# con-left-bot.net
KiCad netlist of a schematic drawn in Altium Designer
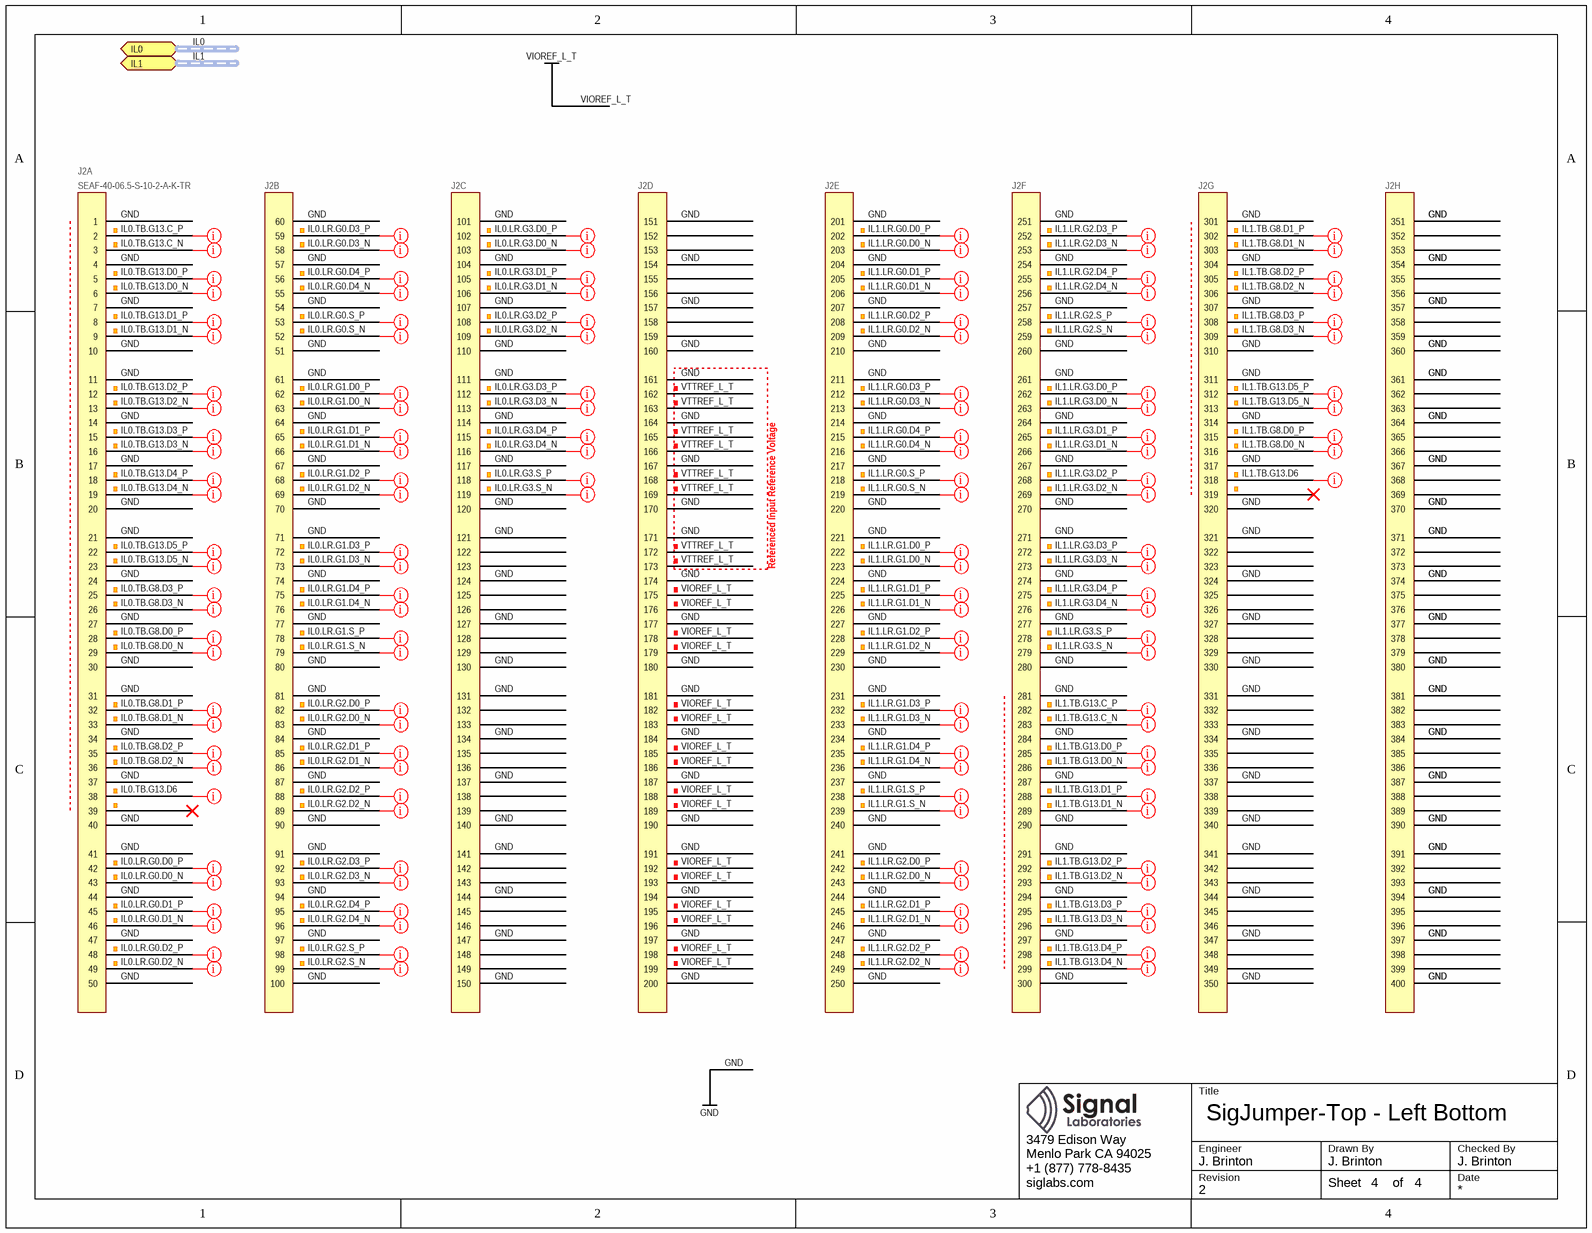
[diagram p0: con-left-bot.SchDoc]

(export (version "E")
  (design (tool "Eeschema 10.0.6"))
  (components
    (comp (ref "J2")
      (value "SEAF-40-06.5-S-10-2-A-K-TR")
      (footprint "samtec:SEAF-40-06.5-S-10-2-A-K-TR")
      (description "Terminal Array Assembly, Surface Mount, 0.050\" Pitch, 400 Pins")
      (fields (field (name "MANUFACTURER") "Samtec"))
      (libsource (lib "samtec") (part "SEAF-40-06.5-S-10-2-A-K-TR"))
    )
  )
  (nets
    (net (code "3") (name "/IL0.LR.G0.D0_N") (class "Default")
      (node (ref "J2") (pin "43") (pinfunction "43_43") (pintype "passive"))
    )
    (net (code "4") (name "/IL0.LR.G0.D0_P") (class "Default")
      (node (ref "J2") (pin "42") (pinfunction "42_42") (pintype "passive"))
    )
    (net (code "5") (name "/IL0.LR.G0.D1_N") (class "Default")
      (node (ref "J2") (pin "46") (pinfunction "46_46") (pintype "passive"))
    )
    (net (code "6") (name "/IL0.LR.G0.D1_P") (class "Default")
      (node (ref "J2") (pin "45") (pinfunction "45_45") (pintype "passive"))
    )
    (net (code "7") (name "/IL0.LR.G0.D2_N") (class "Default")
      (node (ref "J2") (pin "49") (pinfunction "49_49") (pintype "passive"))
    )
    (net (code "8") (name "/IL0.LR.G0.D2_P") (class "Default")
      (node (ref "J2") (pin "48") (pinfunction "48_48") (pintype "passive"))
    )
    (net (code "9") (name "/IL0.LR.G0.D3_N") (class "Default")
      (node (ref "J2") (pin "58") (pinfunction "58_58") (pintype "passive"))
    )
    (net (code "10") (name "/IL0.LR.G0.D3_P") (class "Default")
      (node (ref "J2") (pin "59") (pinfunction "59_59") (pintype "passive"))
    )
    (net (code "11") (name "/IL0.LR.G0.D4_N") (class "Default")
      (node (ref "J2") (pin "55") (pinfunction "55_55") (pintype "passive"))
    )
    (net (code "12") (name "/IL0.LR.G0.D4_P") (class "Default")
      (node (ref "J2") (pin "56") (pinfunction "56_56") (pintype "passive"))
    )
    (net (code "13") (name "/IL0.LR.G0.S_N") (class "Default")
      (node (ref "J2") (pin "52") (pinfunction "52_52") (pintype "passive"))
    )
    (net (code "14") (name "/IL0.LR.G0.S_P") (class "Default")
      (node (ref "J2") (pin "53") (pinfunction "53_53") (pintype "passive"))
    )
    (net (code "15") (name "/IL0.LR.G1.D0_N") (class "Default")
      (node (ref "J2") (pin "63") (pinfunction "63_63") (pintype "passive"))
    )
    (net (code "16") (name "/IL0.LR.G1.D0_P") (class "Default")
      (node (ref "J2") (pin "62") (pinfunction "62_62") (pintype "passive"))
    )
    (net (code "17") (name "/IL0.LR.G1.D1_N") (class "Default")
      (node (ref "J2") (pin "66") (pinfunction "66_66") (pintype "passive"))
    )
    (net (code "18") (name "/IL0.LR.G1.D1_P") (class "Default")
      (node (ref "J2") (pin "65") (pinfunction "65_65") (pintype "passive"))
    )
    (net (code "19") (name "/IL0.LR.G1.D2_N") (class "Default")
      (node (ref "J2") (pin "69") (pinfunction "69_69") (pintype "passive"))
    )
    (net (code "20") (name "/IL0.LR.G1.D2_P") (class "Default")
      (node (ref "J2") (pin "68") (pinfunction "68_68") (pintype "passive"))
    )
    (net (code "21") (name "/IL0.LR.G1.D3_N") (class "Default")
      (node (ref "J2") (pin "73") (pinfunction "73_73") (pintype "passive"))
    )
    (net (code "22") (name "/IL0.LR.G1.D3_P") (class "Default")
      (node (ref "J2") (pin "72") (pinfunction "72_72") (pintype "passive"))
    )
    (net (code "23") (name "/IL0.LR.G1.D4_N") (class "Default")
      (node (ref "J2") (pin "76") (pinfunction "76_76") (pintype "passive"))
    )
    (net (code "24") (name "/IL0.LR.G1.D4_P") (class "Default")
      (node (ref "J2") (pin "75") (pinfunction "75_75") (pintype "passive"))
    )
    (net (code "25") (name "/IL0.LR.G1.S_N") (class "Default")
      (node (ref "J2") (pin "79") (pinfunction "79_79") (pintype "passive"))
    )
    (net (code "26") (name "/IL0.LR.G1.S_P") (class "Default")
      (node (ref "J2") (pin "78") (pinfunction "78_78") (pintype "passive"))
    )
    (net (code "27") (name "/IL0.LR.G2.D0_N") (class "Default")
      (node (ref "J2") (pin "83") (pinfunction "83_83") (pintype "passive"))
    )
    (net (code "28") (name "/IL0.LR.G2.D0_P") (class "Default")
      (node (ref "J2") (pin "82") (pinfunction "82_82") (pintype "passive"))
    )
    (net (code "29") (name "/IL0.LR.G2.D1_N") (class "Default")
      (node (ref "J2") (pin "86") (pinfunction "86_86") (pintype "passive"))
    )
    (net (code "30") (name "/IL0.LR.G2.D1_P") (class "Default")
      (node (ref "J2") (pin "85") (pinfunction "85_85") (pintype "passive"))
    )
    (net (code "31") (name "/IL0.LR.G2.D2_N") (class "Default")
      (node (ref "J2") (pin "89") (pinfunction "89_89") (pintype "passive"))
    )
    (net (code "32") (name "/IL0.LR.G2.D2_P") (class "Default")
      (node (ref "J2") (pin "88") (pinfunction "88_88") (pintype "passive"))
    )
    (net (code "33") (name "/IL0.LR.G2.D3_N") (class "Default")
      (node (ref "J2") (pin "93") (pinfunction "93_93") (pintype "passive"))
    )
    (net (code "34") (name "/IL0.LR.G2.D3_P") (class "Default")
      (node (ref "J2") (pin "92") (pinfunction "92_92") (pintype "passive"))
    )
    (net (code "35") (name "/IL0.LR.G2.D4_N") (class "Default")
      (node (ref "J2") (pin "96") (pinfunction "96_96") (pintype "passive"))
    )
    (net (code "36") (name "/IL0.LR.G2.D4_P") (class "Default")
      (node (ref "J2") (pin "95") (pinfunction "95_95") (pintype "passive"))
    )
    (net (code "37") (name "/IL0.LR.G2.S_N") (class "Default")
      (node (ref "J2") (pin "99") (pinfunction "99_99") (pintype "passive"))
    )
    (net (code "38") (name "/IL0.LR.G2.S_P") (class "Default")
      (node (ref "J2") (pin "98") (pinfunction "98_98") (pintype "passive"))
    )
    (net (code "39") (name "/IL0.LR.G3.D0_N") (class "Default")
      (node (ref "J2") (pin "103") (pinfunction "103_103") (pintype "passive"))
    )
    (net (code "40") (name "/IL0.LR.G3.D0_P") (class "Default")
      (node (ref "J2") (pin "102") (pinfunction "102_102") (pintype "passive"))
    )
    (net (code "41") (name "/IL0.LR.G3.D1_N") (class "Default")
      (node (ref "J2") (pin "106") (pinfunction "106_106") (pintype "passive"))
    )
    (net (code "42") (name "/IL0.LR.G3.D1_P") (class "Default")
      (node (ref "J2") (pin "105") (pinfunction "105_105") (pintype "passive"))
    )
    (net (code "43") (name "/IL0.LR.G3.D2_N") (class "Default")
      (node (ref "J2") (pin "109") (pinfunction "109_109") (pintype "passive"))
    )
    (net (code "44") (name "/IL0.LR.G3.D2_P") (class "Default")
      (node (ref "J2") (pin "108") (pinfunction "108_108") (pintype "passive"))
    )
    (net (code "45") (name "/IL0.LR.G3.D3_N") (class "Default")
      (node (ref "J2") (pin "113") (pinfunction "113_113") (pintype "passive"))
    )
    (net (code "46") (name "/IL0.LR.G3.D3_P") (class "Default")
      (node (ref "J2") (pin "112") (pinfunction "112_112") (pintype "passive"))
    )
    (net (code "47") (name "/IL0.LR.G3.D4_N") (class "Default")
      (node (ref "J2") (pin "116") (pinfunction "116_116") (pintype "passive"))
    )
    (net (code "48") (name "/IL0.LR.G3.D4_P") (class "Default")
      (node (ref "J2") (pin "115") (pinfunction "115_115") (pintype "passive"))
    )
    (net (code "49") (name "/IL0.LR.G3.S_N") (class "Default")
      (node (ref "J2") (pin "119") (pinfunction "119_119") (pintype "passive"))
    )
    (net (code "50") (name "/IL0.LR.G3.S_P") (class "Default")
      (node (ref "J2") (pin "118") (pinfunction "118_118") (pintype "passive"))
    )
    (net (code "51") (name "/IL0.TB.G8.D0_N") (class "Default")
      (node (ref "J2") (pin "29") (pinfunction "29_29") (pintype "passive"))
    )
    (net (code "52") (name "/IL0.TB.G8.D0_P") (class "Default")
      (node (ref "J2") (pin "28") (pinfunction "28_28") (pintype "passive"))
    )
    (net (code "53") (name "/IL0.TB.G8.D1_N") (class "Default")
      (node (ref "J2") (pin "33") (pinfunction "33_33") (pintype "passive"))
    )
    (net (code "54") (name "/IL0.TB.G8.D1_P") (class "Default")
      (node (ref "J2") (pin "32") (pinfunction "32_32") (pintype "passive"))
    )
    (net (code "55") (name "/IL0.TB.G8.D2_N") (class "Default")
      (node (ref "J2") (pin "36") (pinfunction "36_36") (pintype "passive"))
    )
    (net (code "56") (name "/IL0.TB.G8.D2_P") (class "Default")
      (node (ref "J2") (pin "35") (pinfunction "35_35") (pintype "passive"))
    )
    (net (code "57") (name "/IL0.TB.G8.D3_N") (class "Default")
      (node (ref "J2") (pin "26") (pinfunction "26_26") (pintype "passive"))
    )
    (net (code "58") (name "/IL0.TB.G8.D3_P") (class "Default")
      (node (ref "J2") (pin "25") (pinfunction "25_25") (pintype "passive"))
    )
    (net (code "59") (name "/IL0.TB.G13.C_N") (class "Default")
      (node (ref "J2") (pin "3") (pinfunction "3_3") (pintype "passive"))
    )
    (net (code "60") (name "/IL0.TB.G13.C_P") (class "Default")
      (node (ref "J2") (pin "2") (pinfunction "2_2") (pintype "passive"))
    )
    (net (code "61") (name "/IL0.TB.G13.D0_N") (class "Default")
      (node (ref "J2") (pin "6") (pinfunction "6_6") (pintype "passive"))
    )
    (net (code "62") (name "/IL0.TB.G13.D0_P") (class "Default")
      (node (ref "J2") (pin "5") (pinfunction "5_5") (pintype "passive"))
    )
    (net (code "63") (name "/IL0.TB.G13.D1_N") (class "Default")
      (node (ref "J2") (pin "9") (pinfunction "9_9") (pintype "passive"))
    )
    (net (code "64") (name "/IL0.TB.G13.D1_P") (class "Default")
      (node (ref "J2") (pin "8") (pinfunction "8_8") (pintype "passive"))
    )
    (net (code "65") (name "/IL0.TB.G13.D2_N") (class "Default")
      (node (ref "J2") (pin "13") (pinfunction "13_13") (pintype "passive"))
    )
    (net (code "66") (name "/IL0.TB.G13.D2_P") (class "Default")
      (node (ref "J2") (pin "12") (pinfunction "12_12") (pintype "passive"))
    )
    (net (code "67") (name "/IL0.TB.G13.D3_N") (class "Default")
      (node (ref "J2") (pin "16") (pinfunction "16_16") (pintype "passive"))
    )
    (net (code "68") (name "/IL0.TB.G13.D3_P") (class "Default")
      (node (ref "J2") (pin "15") (pinfunction "15_15") (pintype "passive"))
    )
    (net (code "69") (name "/IL0.TB.G13.D4_N") (class "Default")
      (node (ref "J2") (pin "19") (pinfunction "19_19") (pintype "passive"))
    )
    (net (code "70") (name "/IL0.TB.G13.D4_P") (class "Default")
      (node (ref "J2") (pin "18") (pinfunction "18_18") (pintype "passive"))
    )
    (net (code "71") (name "/IL0.TB.G13.D5_N") (class "Default")
      (node (ref "J2") (pin "23") (pinfunction "23_23") (pintype "passive"))
    )
    (net (code "72") (name "/IL0.TB.G13.D5_P") (class "Default")
      (node (ref "J2") (pin "22") (pinfunction "22_22") (pintype "passive"))
    )
    (net (code "73") (name "/IL0.TB.G13.D6") (class "Default")
      (node (ref "J2") (pin "38") (pinfunction "38_38") (pintype "passive"))
    )
    (net (code "74") (name "/IL1.LR.G0.D0_N") (class "Default")
      (node (ref "J2") (pin "203") (pinfunction "203_203") (pintype "passive"))
    )
    (net (code "75") (name "/IL1.LR.G0.D0_P") (class "Default")
      (node (ref "J2") (pin "202") (pinfunction "202_202") (pintype "passive"))
    )
    (net (code "76") (name "/IL1.LR.G0.D1_N") (class "Default")
      (node (ref "J2") (pin "206") (pinfunction "206_206") (pintype "passive"))
    )
    (net (code "77") (name "/IL1.LR.G0.D1_P") (class "Default")
      (node (ref "J2") (pin "205") (pinfunction "205_205") (pintype "passive"))
    )
    (net (code "78") (name "/IL1.LR.G0.D2_N") (class "Default")
      (node (ref "J2") (pin "209") (pinfunction "209_209") (pintype "passive"))
    )
    (net (code "79") (name "/IL1.LR.G0.D2_P") (class "Default")
      (node (ref "J2") (pin "208") (pinfunction "208_208") (pintype "passive"))
    )
    (net (code "80") (name "/IL1.LR.G0.D3_N") (class "Default")
      (node (ref "J2") (pin "213") (pinfunction "213_213") (pintype "passive"))
    )
    (net (code "81") (name "/IL1.LR.G0.D3_P") (class "Default")
      (node (ref "J2") (pin "212") (pinfunction "212_212") (pintype "passive"))
    )
    (net (code "82") (name "/IL1.LR.G0.D4_N") (class "Default")
      (node (ref "J2") (pin "216") (pinfunction "216_216") (pintype "passive"))
    )
    (net (code "83") (name "/IL1.LR.G0.D4_P") (class "Default")
      (node (ref "J2") (pin "215") (pinfunction "215_215") (pintype "passive"))
    )
    (net (code "84") (name "/IL1.LR.G0.S_N") (class "Default")
      (node (ref "J2") (pin "219") (pinfunction "219_219") (pintype "passive"))
    )
    (net (code "85") (name "/IL1.LR.G0.S_P") (class "Default")
      (node (ref "J2") (pin "218") (pinfunction "218_218") (pintype "passive"))
    )
    (net (code "86") (name "/IL1.LR.G1.D0_N") (class "Default")
      (node (ref "J2") (pin "223") (pinfunction "223_223") (pintype "passive"))
    )
    (net (code "87") (name "/IL1.LR.G1.D0_P") (class "Default")
      (node (ref "J2") (pin "222") (pinfunction "222_222") (pintype "passive"))
    )
    (net (code "88") (name "/IL1.LR.G1.D1_N") (class "Default")
      (node (ref "J2") (pin "226") (pinfunction "226_226") (pintype "passive"))
    )
    (net (code "89") (name "/IL1.LR.G1.D1_P") (class "Default")
      (node (ref "J2") (pin "225") (pinfunction "225_225") (pintype "passive"))
    )
    (net (code "90") (name "/IL1.LR.G1.D2_N") (class "Default")
      (node (ref "J2") (pin "229") (pinfunction "229_229") (pintype "passive"))
    )
    (net (code "91") (name "/IL1.LR.G1.D2_P") (class "Default")
      (node (ref "J2") (pin "228") (pinfunction "228_228") (pintype "passive"))
    )
    (net (code "92") (name "/IL1.LR.G1.D3_N") (class "Default")
      (node (ref "J2") (pin "233") (pinfunction "233_233") (pintype "passive"))
    )
    (net (code "93") (name "/IL1.LR.G1.D3_P") (class "Default")
      (node (ref "J2") (pin "232") (pinfunction "232_232") (pintype "passive"))
    )
    (net (code "94") (name "/IL1.LR.G1.D4_N") (class "Default")
      (node (ref "J2") (pin "236") (pinfunction "236_236") (pintype "passive"))
    )
    (net (code "95") (name "/IL1.LR.G1.D4_P") (class "Default")
      (node (ref "J2") (pin "235") (pinfunction "235_235") (pintype "passive"))
    )
    (net (code "96") (name "/IL1.LR.G1.S_N") (class "Default")
      (node (ref "J2") (pin "239") (pinfunction "239_239") (pintype "passive"))
    )
    (net (code "97") (name "/IL1.LR.G1.S_P") (class "Default")
      (node (ref "J2") (pin "238") (pinfunction "238_238") (pintype "passive"))
    )
    (net (code "98") (name "/IL1.LR.G2.D0_N") (class "Default")
      (node (ref "J2") (pin "243") (pinfunction "243_243") (pintype "passive"))
    )
    (net (code "99") (name "/IL1.LR.G2.D0_P") (class "Default")
      (node (ref "J2") (pin "242") (pinfunction "242_242") (pintype "passive"))
    )
    (net (code "100") (name "/IL1.LR.G2.D1_N") (class "Default")
      (node (ref "J2") (pin "246") (pinfunction "246_246") (pintype "passive"))
    )
    (net (code "101") (name "/IL1.LR.G2.D1_P") (class "Default")
      (node (ref "J2") (pin "245") (pinfunction "245_245") (pintype "passive"))
    )
    (net (code "102") (name "/IL1.LR.G2.D2_N") (class "Default")
      (node (ref "J2") (pin "249") (pinfunction "249_249") (pintype "passive"))
    )
    (net (code "103") (name "/IL1.LR.G2.D2_P") (class "Default")
      (node (ref "J2") (pin "248") (pinfunction "248_248") (pintype "passive"))
    )
    (net (code "104") (name "/IL1.LR.G2.D3_N") (class "Default")
      (node (ref "J2") (pin "253") (pinfunction "253_253") (pintype "passive"))
    )
    (net (code "105") (name "/IL1.LR.G2.D3_P") (class "Default")
      (node (ref "J2") (pin "252") (pinfunction "252_252") (pintype "passive"))
    )
    (net (code "106") (name "/IL1.LR.G2.D4_N") (class "Default")
      (node (ref "J2") (pin "256") (pinfunction "256_256") (pintype "passive"))
    )
    (net (code "107") (name "/IL1.LR.G2.D4_P") (class "Default")
      (node (ref "J2") (pin "255") (pinfunction "255_255") (pintype "passive"))
    )
    (net (code "108") (name "/IL1.LR.G2.S_N") (class "Default")
      (node (ref "J2") (pin "259") (pinfunction "259_259") (pintype "passive"))
    )
    (net (code "109") (name "/IL1.LR.G2.S_P") (class "Default")
      (node (ref "J2") (pin "258") (pinfunction "258_258") (pintype "passive"))
    )
    (net (code "110") (name "/IL1.LR.G3.D0_N") (class "Default")
      (node (ref "J2") (pin "263") (pinfunction "263_263") (pintype "passive"))
    )
    (net (code "111") (name "/IL1.LR.G3.D0_P") (class "Default")
      (node (ref "J2") (pin "262") (pinfunction "262_262") (pintype "passive"))
    )
    (net (code "112") (name "/IL1.LR.G3.D1_N") (class "Default")
      (node (ref "J2") (pin "266") (pinfunction "266_266") (pintype "passive"))
    )
    (net (code "113") (name "/IL1.LR.G3.D1_P") (class "Default")
      (node (ref "J2") (pin "265") (pinfunction "265_265") (pintype "passive"))
    )
    (net (code "114") (name "/IL1.LR.G3.D2_N") (class "Default")
      (node (ref "J2") (pin "269") (pinfunction "269_269") (pintype "passive"))
    )
    (net (code "115") (name "/IL1.LR.G3.D2_P") (class "Default")
      (node (ref "J2") (pin "268") (pinfunction "268_268") (pintype "passive"))
    )
    (net (code "116") (name "/IL1.LR.G3.D3_N") (class "Default")
      (node (ref "J2") (pin "273") (pinfunction "273_273") (pintype "passive"))
    )
    (net (code "117") (name "/IL1.LR.G3.D3_P") (class "Default")
      (node (ref "J2") (pin "272") (pinfunction "272_272") (pintype "passive"))
    )
    (net (code "118") (name "/IL1.LR.G3.D4_N") (class "Default")
      (node (ref "J2") (pin "276") (pinfunction "276_276") (pintype "passive"))
    )
    (net (code "119") (name "/IL1.LR.G3.D4_P") (class "Default")
      (node (ref "J2") (pin "275") (pinfunction "275_275") (pintype "passive"))
    )
    (net (code "120") (name "/IL1.LR.G3.S_N") (class "Default")
      (node (ref "J2") (pin "279") (pinfunction "279_279") (pintype "passive"))
    )
    (net (code "121") (name "/IL1.LR.G3.S_P") (class "Default")
      (node (ref "J2") (pin "278") (pinfunction "278_278") (pintype "passive"))
    )
    (net (code "122") (name "/IL1.TB.G8.D0_N") (class "Default")
      (node (ref "J2") (pin "316") (pinfunction "316_316") (pintype "passive"))
    )
    (net (code "123") (name "/IL1.TB.G8.D0_P") (class "Default")
      (node (ref "J2") (pin "315") (pinfunction "315_315") (pintype "passive"))
    )
    (net (code "124") (name "/IL1.TB.G8.D1_N") (class "Default")
      (node (ref "J2") (pin "303") (pinfunction "303_303") (pintype "passive"))
    )
    (net (code "125") (name "/IL1.TB.G8.D1_P") (class "Default")
      (node (ref "J2") (pin "302") (pinfunction "302_302") (pintype "passive"))
    )
    (net (code "126") (name "/IL1.TB.G8.D2_N") (class "Default")
      (node (ref "J2") (pin "306") (pinfunction "306_306") (pintype "passive"))
    )
    (net (code "127") (name "/IL1.TB.G8.D2_P") (class "Default")
      (node (ref "J2") (pin "305") (pinfunction "305_305") (pintype "passive"))
    )
    (net (code "128") (name "/IL1.TB.G8.D3_N") (class "Default")
      (node (ref "J2") (pin "309") (pinfunction "309_309") (pintype "passive"))
    )
    (net (code "129") (name "/IL1.TB.G8.D3_P") (class "Default")
      (node (ref "J2") (pin "308") (pinfunction "308_308") (pintype "passive"))
    )
    (net (code "130") (name "/IL1.TB.G13.C_N") (class "Default")
      (node (ref "J2") (pin "283") (pinfunction "283_283") (pintype "passive"))
    )
    (net (code "131") (name "/IL1.TB.G13.C_P") (class "Default")
      (node (ref "J2") (pin "282") (pinfunction "282_282") (pintype "passive"))
    )
    (net (code "132") (name "/IL1.TB.G13.D0_N") (class "Default")
      (node (ref "J2") (pin "286") (pinfunction "286_286") (pintype "passive"))
    )
    (net (code "133") (name "/IL1.TB.G13.D0_P") (class "Default")
      (node (ref "J2") (pin "285") (pinfunction "285_285") (pintype "passive"))
    )
    (net (code "134") (name "/IL1.TB.G13.D1_N") (class "Default")
      (node (ref "J2") (pin "289") (pinfunction "289_289") (pintype "passive"))
    )
    (net (code "135") (name "/IL1.TB.G13.D1_P") (class "Default")
      (node (ref "J2") (pin "288") (pinfunction "288_288") (pintype "passive"))
    )
    (net (code "136") (name "/IL1.TB.G13.D2_N") (class "Default")
      (node (ref "J2") (pin "293") (pinfunction "293_293") (pintype "passive"))
    )
    (net (code "137") (name "/IL1.TB.G13.D2_P") (class "Default")
      (node (ref "J2") (pin "292") (pinfunction "292_292") (pintype "passive"))
    )
    (net (code "138") (name "/IL1.TB.G13.D3_N") (class "Default")
      (node (ref "J2") (pin "296") (pinfunction "296_296") (pintype "passive"))
    )
    (net (code "139") (name "/IL1.TB.G13.D3_P") (class "Default")
      (node (ref "J2") (pin "295") (pinfunction "295_295") (pintype "passive"))
    )
    (net (code "140") (name "/IL1.TB.G13.D4_N") (class "Default")
      (node (ref "J2") (pin "299") (pinfunction "299_299") (pintype "passive"))
    )
    (net (code "141") (name "/IL1.TB.G13.D4_P") (class "Default")
      (node (ref "J2") (pin "298") (pinfunction "298_298") (pintype "passive"))
    )
    (net (code "142") (name "/IL1.TB.G13.D5_N") (class "Default")
      (node (ref "J2") (pin "313") (pinfunction "313_313") (pintype "passive"))
    )
    (net (code "143") (name "/IL1.TB.G13.D5_P") (class "Default")
      (node (ref "J2") (pin "312") (pinfunction "312_312") (pintype "passive"))
    )
    (net (code "144") (name "/IL1.TB.G13.D6") (class "Default")
      (node (ref "J2") (pin "318") (pinfunction "318_318") (pintype "passive"))
    )
    (net (code "145") (name "/VTTREF_L_T") (class "Default")
      (node (ref "J2") (pin "162") (pinfunction "162_162") (pintype "passive"))
      (node (ref "J2") (pin "163") (pinfunction "163_163") (pintype "passive"))
      (node (ref "J2") (pin "165") (pinfunction "165_165") (pintype "passive"))
      (node (ref "J2") (pin "166") (pinfunction "166_166") (pintype "passive"))
      (node (ref "J2") (pin "168") (pinfunction "168_168") (pintype "passive"))
      (node (ref "J2") (pin "169") (pinfunction "169_169") (pintype "passive"))
      (node (ref "J2") (pin "172") (pinfunction "172_172") (pintype "passive"))
      (node (ref "J2") (pin "173") (pinfunction "173_173") (pintype "passive"))
    )
    (net (code "148") (name "GND") (class "Default")
      (node (ref "J2") (pin "1") (pinfunction "1_1") (pintype "passive"))
      (node (ref "J2") (pin "10") (pinfunction "10_10") (pintype "passive"))
      (node (ref "J2") (pin "100") (pinfunction "100_100") (pintype "passive"))
      (node (ref "J2") (pin "101") (pinfunction "101_101") (pintype "passive"))
      (node (ref "J2") (pin "104") (pinfunction "104_104") (pintype "passive"))
      (node (ref "J2") (pin "107") (pinfunction "107_107") (pintype "passive"))
      (node (ref "J2") (pin "11") (pinfunction "11_11") (pintype "passive"))
      (node (ref "J2") (pin "110") (pinfunction "110_110") (pintype "passive"))
      (node (ref "J2") (pin "111") (pinfunction "111_111") (pintype "passive"))
      (node (ref "J2") (pin "114") (pinfunction "114_114") (pintype "passive"))
      (node (ref "J2") (pin "117") (pinfunction "117_117") (pintype "passive"))
      (node (ref "J2") (pin "120") (pinfunction "120_120") (pintype "passive"))
      (node (ref "J2") (pin "121") (pinfunction "121_121") (pintype "passive"))
      (node (ref "J2") (pin "124") (pinfunction "124_124") (pintype "passive"))
      (node (ref "J2") (pin "127") (pinfunction "127_127") (pintype "passive"))
      (node (ref "J2") (pin "130") (pinfunction "130_130") (pintype "passive"))
      (node (ref "J2") (pin "131") (pinfunction "131_131") (pintype "passive"))
      (node (ref "J2") (pin "134") (pinfunction "134_134") (pintype "passive"))
      (node (ref "J2") (pin "137") (pinfunction "137_137") (pintype "passive"))
      (node (ref "J2") (pin "14") (pinfunction "14_14") (pintype "passive"))
      (node (ref "J2") (pin "140") (pinfunction "140_140") (pintype "passive"))
      (node (ref "J2") (pin "141") (pinfunction "141_141") (pintype "passive"))
      (node (ref "J2") (pin "144") (pinfunction "144_144") (pintype "passive"))
      (node (ref "J2") (pin "147") (pinfunction "147_147") (pintype "passive"))
      (node (ref "J2") (pin "150") (pinfunction "150_150") (pintype "passive"))
      (node (ref "J2") (pin "151") (pinfunction "151_151") (pintype "passive"))
      (node (ref "J2") (pin "154") (pinfunction "154_154") (pintype "passive"))
      (node (ref "J2") (pin "157") (pinfunction "157_157") (pintype "passive"))
      (node (ref "J2") (pin "160") (pinfunction "160_160") (pintype "passive"))
      (node (ref "J2") (pin "161") (pinfunction "161_161") (pintype "passive"))
      (node (ref "J2") (pin "164") (pinfunction "164_164") (pintype "passive"))
      (node (ref "J2") (pin "167") (pinfunction "167_167") (pintype "passive"))
      (node (ref "J2") (pin "17") (pinfunction "17_17") (pintype "passive"))
      (node (ref "J2") (pin "170") (pinfunction "170_170") (pintype "passive"))
      (node (ref "J2") (pin "171") (pinfunction "171_171") (pintype "passive"))
      (node (ref "J2") (pin "174") (pinfunction "174_174") (pintype "passive"))
      (node (ref "J2") (pin "177") (pinfunction "177_177") (pintype "passive"))
      (node (ref "J2") (pin "180") (pinfunction "180_180") (pintype "passive"))
      (node (ref "J2") (pin "181") (pinfunction "181_181") (pintype "passive"))
      (node (ref "J2") (pin "184") (pinfunction "184_184") (pintype "passive"))
      (node (ref "J2") (pin "187") (pinfunction "187_187") (pintype "passive"))
      (node (ref "J2") (pin "190") (pinfunction "190_190") (pintype "passive"))
      (node (ref "J2") (pin "191") (pinfunction "191_191") (pintype "passive"))
      (node (ref "J2") (pin "194") (pinfunction "194_194") (pintype "passive"))
      (node (ref "J2") (pin "197") (pinfunction "197_197") (pintype "passive"))
      (node (ref "J2") (pin "20") (pinfunction "20_20") (pintype "passive"))
      (node (ref "J2") (pin "200") (pinfunction "200_200") (pintype "passive"))
      (node (ref "J2") (pin "201") (pinfunction "201_201") (pintype "passive"))
      (node (ref "J2") (pin "204") (pinfunction "204_204") (pintype "passive"))
      (node (ref "J2") (pin "207") (pinfunction "207_207") (pintype "passive"))
      (node (ref "J2") (pin "21") (pinfunction "21_21") (pintype "passive"))
      (node (ref "J2") (pin "210") (pinfunction "210_210") (pintype "passive"))
      (node (ref "J2") (pin "211") (pinfunction "211_211") (pintype "passive"))
      (node (ref "J2") (pin "214") (pinfunction "214_214") (pintype "passive"))
      (node (ref "J2") (pin "217") (pinfunction "217_217") (pintype "passive"))
      (node (ref "J2") (pin "220") (pinfunction "220_220") (pintype "passive"))
      (node (ref "J2") (pin "221") (pinfunction "221_221") (pintype "passive"))
      (node (ref "J2") (pin "224") (pinfunction "224_224") (pintype "passive"))
      (node (ref "J2") (pin "227") (pinfunction "227_227") (pintype "passive"))
      (node (ref "J2") (pin "230") (pinfunction "230_230") (pintype "passive"))
      (node (ref "J2") (pin "231") (pinfunction "231_231") (pintype "passive"))
      (node (ref "J2") (pin "234") (pinfunction "234_234") (pintype "passive"))
      (node (ref "J2") (pin "237") (pinfunction "237_237") (pintype "passive"))
      (node (ref "J2") (pin "24") (pinfunction "24_24") (pintype "passive"))
      (node (ref "J2") (pin "240") (pinfunction "240_240") (pintype "passive"))
      (node (ref "J2") (pin "241") (pinfunction "241_241") (pintype "passive"))
      (node (ref "J2") (pin "244") (pinfunction "244_244") (pintype "passive"))
      (node (ref "J2") (pin "247") (pinfunction "247_247") (pintype "passive"))
      (node (ref "J2") (pin "250") (pinfunction "250_250") (pintype "passive"))
      (node (ref "J2") (pin "251") (pinfunction "251_251") (pintype "passive"))
      (node (ref "J2") (pin "254") (pinfunction "254_254") (pintype "passive"))
      (node (ref "J2") (pin "257") (pinfunction "257_257") (pintype "passive"))
      (node (ref "J2") (pin "260") (pinfunction "260_260") (pintype "passive"))
      (node (ref "J2") (pin "261") (pinfunction "261_261") (pintype "passive"))
      (node (ref "J2") (pin "264") (pinfunction "264_264") (pintype "passive"))
      (node (ref "J2") (pin "267") (pinfunction "267_267") (pintype "passive"))
      (node (ref "J2") (pin "27") (pinfunction "27_27") (pintype "passive"))
      (node (ref "J2") (pin "270") (pinfunction "270_270") (pintype "passive"))
      (node (ref "J2") (pin "271") (pinfunction "271_271") (pintype "passive"))
      (node (ref "J2") (pin "274") (pinfunction "274_274") (pintype "passive"))
      (node (ref "J2") (pin "277") (pinfunction "277_277") (pintype "passive"))
      (node (ref "J2") (pin "280") (pinfunction "280_280") (pintype "passive"))
      (node (ref "J2") (pin "281") (pinfunction "281_281") (pintype "passive"))
      (node (ref "J2") (pin "284") (pinfunction "284_284") (pintype "passive"))
      (node (ref "J2") (pin "287") (pinfunction "287_287") (pintype "passive"))
      (node (ref "J2") (pin "290") (pinfunction "290_290") (pintype "passive"))
      (node (ref "J2") (pin "291") (pinfunction "291_291") (pintype "passive"))
      (node (ref "J2") (pin "294") (pinfunction "294_294") (pintype "passive"))
      (node (ref "J2") (pin "297") (pinfunction "297_297") (pintype "passive"))
      (node (ref "J2") (pin "30") (pinfunction "30_30") (pintype "passive"))
      (node (ref "J2") (pin "300") (pinfunction "300_300") (pintype "passive"))
      (node (ref "J2") (pin "301") (pinfunction "301_301") (pintype "passive"))
      (node (ref "J2") (pin "304") (pinfunction "304_304") (pintype "passive"))
      (node (ref "J2") (pin "307") (pinfunction "307_307") (pintype "passive"))
      (node (ref "J2") (pin "31") (pinfunction "31_31") (pintype "passive"))
      (node (ref "J2") (pin "310") (pinfunction "310_310") (pintype "passive"))
      (node (ref "J2") (pin "311") (pinfunction "311_311") (pintype "passive"))
      (node (ref "J2") (pin "314") (pinfunction "314_314") (pintype "passive"))
      (node (ref "J2") (pin "317") (pinfunction "317_317") (pintype "passive"))
      (node (ref "J2") (pin "320") (pinfunction "320_320") (pintype "passive"))
      (node (ref "J2") (pin "321") (pinfunction "321_321") (pintype "passive"))
      (node (ref "J2") (pin "324") (pinfunction "324_324") (pintype "passive"))
      (node (ref "J2") (pin "327") (pinfunction "327_327") (pintype "passive"))
      (node (ref "J2") (pin "330") (pinfunction "330_330") (pintype "passive"))
      (node (ref "J2") (pin "331") (pinfunction "331_331") (pintype "passive"))
      (node (ref "J2") (pin "334") (pinfunction "334_334") (pintype "passive"))
      (node (ref "J2") (pin "337") (pinfunction "337_337") (pintype "passive"))
      (node (ref "J2") (pin "34") (pinfunction "34_34") (pintype "passive"))
      (node (ref "J2") (pin "340") (pinfunction "340_340") (pintype "passive"))
      (node (ref "J2") (pin "341") (pinfunction "341_341") (pintype "passive"))
      (node (ref "J2") (pin "344") (pinfunction "344_344") (pintype "passive"))
      (node (ref "J2") (pin "347") (pinfunction "347_347") (pintype "passive"))
      (node (ref "J2") (pin "350") (pinfunction "350_350") (pintype "passive"))
      (node (ref "J2") (pin "351") (pinfunction "351_351") (pintype "passive"))
      (node (ref "J2") (pin "354") (pinfunction "354_354") (pintype "passive"))
      (node (ref "J2") (pin "357") (pinfunction "357_357") (pintype "passive"))
      (node (ref "J2") (pin "360") (pinfunction "360_360") (pintype "passive"))
      (node (ref "J2") (pin "361") (pinfunction "361_361") (pintype "passive"))
      (node (ref "J2") (pin "364") (pinfunction "364_364") (pintype "passive"))
      (node (ref "J2") (pin "367") (pinfunction "367_367") (pintype "passive"))
      (node (ref "J2") (pin "37") (pinfunction "37_37") (pintype "passive"))
      (node (ref "J2") (pin "370") (pinfunction "370_370") (pintype "passive"))
      (node (ref "J2") (pin "371") (pinfunction "371_371") (pintype "passive"))
      (node (ref "J2") (pin "374") (pinfunction "374_374") (pintype "passive"))
      (node (ref "J2") (pin "377") (pinfunction "377_377") (pintype "passive"))
      (node (ref "J2") (pin "380") (pinfunction "380_380") (pintype "passive"))
      (node (ref "J2") (pin "381") (pinfunction "381_381") (pintype "passive"))
      (node (ref "J2") (pin "384") (pinfunction "384_384") (pintype "passive"))
      (node (ref "J2") (pin "387") (pinfunction "387_387") (pintype "passive"))
      (node (ref "J2") (pin "390") (pinfunction "390_390") (pintype "passive"))
      (node (ref "J2") (pin "391") (pinfunction "391_391") (pintype "passive"))
      (node (ref "J2") (pin "394") (pinfunction "394_394") (pintype "passive"))
      (node (ref "J2") (pin "397") (pinfunction "397_397") (pintype "passive"))
      (node (ref "J2") (pin "4") (pinfunction "4_4") (pintype "passive"))
      (node (ref "J2") (pin "40") (pinfunction "40_40") (pintype "passive"))
      (node (ref "J2") (pin "400") (pinfunction "400_400") (pintype "passive"))
      (node (ref "J2") (pin "41") (pinfunction "41_41") (pintype "passive"))
      (node (ref "J2") (pin "44") (pinfunction "44_44") (pintype "passive"))
      (node (ref "J2") (pin "47") (pinfunction "47_47") (pintype "passive"))
      (node (ref "J2") (pin "50") (pinfunction "50_50") (pintype "passive"))
      (node (ref "J2") (pin "51") (pinfunction "51_51") (pintype "passive"))
      (node (ref "J2") (pin "54") (pinfunction "54_54") (pintype "passive"))
      (node (ref "J2") (pin "57") (pinfunction "57_57") (pintype "passive"))
      (node (ref "J2") (pin "60") (pinfunction "60_60") (pintype "passive"))
      (node (ref "J2") (pin "61") (pinfunction "61_61") (pintype "passive"))
      (node (ref "J2") (pin "64") (pinfunction "64_64") (pintype "passive"))
      (node (ref "J2") (pin "67") (pinfunction "67_67") (pintype "passive"))
      (node (ref "J2") (pin "7") (pinfunction "7_7") (pintype "passive"))
      (node (ref "J2") (pin "70") (pinfunction "70_70") (pintype "passive"))
      (node (ref "J2") (pin "71") (pinfunction "71_71") (pintype "passive"))
      (node (ref "J2") (pin "74") (pinfunction "74_74") (pintype "passive"))
      (node (ref "J2") (pin "77") (pinfunction "77_77") (pintype "passive"))
      (node (ref "J2") (pin "80") (pinfunction "80_80") (pintype "passive"))
      (node (ref "J2") (pin "81") (pinfunction "81_81") (pintype "passive"))
      (node (ref "J2") (pin "84") (pinfunction "84_84") (pintype "passive"))
      (node (ref "J2") (pin "87") (pinfunction "87_87") (pintype "passive"))
      (node (ref "J2") (pin "90") (pinfunction "90_90") (pintype "passive"))
      (node (ref "J2") (pin "91") (pinfunction "91_91") (pintype "passive"))
      (node (ref "J2") (pin "94") (pinfunction "94_94") (pintype "passive"))
      (node (ref "J2") (pin "97") (pinfunction "97_97") (pintype "passive"))
    )
    (net (code "149") (name "VIOREF_L_T") (class "Default")
      (node (ref "J2") (pin "175") (pinfunction "175_175") (pintype "passive"))
      (node (ref "J2") (pin "176") (pinfunction "176_176") (pintype "passive"))
      (node (ref "J2") (pin "178") (pinfunction "178_178") (pintype "passive"))
      (node (ref "J2") (pin "179") (pinfunction "179_179") (pintype "passive"))
      (node (ref "J2") (pin "182") (pinfunction "182_182") (pintype "passive"))
      (node (ref "J2") (pin "183") (pinfunction "183_183") (pintype "passive"))
      (node (ref "J2") (pin "185") (pinfunction "185_185") (pintype "passive"))
      (node (ref "J2") (pin "186") (pinfunction "186_186") (pintype "passive"))
      (node (ref "J2") (pin "188") (pinfunction "188_188") (pintype "passive"))
      (node (ref "J2") (pin "189") (pinfunction "189_189") (pintype "passive"))
      (node (ref "J2") (pin "192") (pinfunction "192_192") (pintype "passive"))
      (node (ref "J2") (pin "193") (pinfunction "193_193") (pintype "passive"))
      (node (ref "J2") (pin "195") (pinfunction "195_195") (pintype "passive"))
      (node (ref "J2") (pin "196") (pinfunction "196_196") (pintype "passive"))
      (node (ref "J2") (pin "198") (pinfunction "198_198") (pintype "passive"))
      (node (ref "J2") (pin "199") (pinfunction "199_199") (pintype "passive"))
    )
    (net (code "150") (name "unconnected-(J2-Pad39)") (class "Default")
      (node (ref "J2") (pin "39") (pinfunction "39_39") (pintype "passive+no_connect"))
    )
    (net (code "151") (name "unconnected-(J2-Pad122)") (class "Default")
      (node (ref "J2") (pin "122") (pinfunction "122_122") (pintype "passive"))
    )
    (net (code "152") (name "unconnected-(J2-Pad123)") (class "Default")
      (node (ref "J2") (pin "123") (pinfunction "123_123") (pintype "passive"))
    )
    (net (code "153") (name "unconnected-(J2-Pad125)") (class "Default")
      (node (ref "J2") (pin "125") (pinfunction "125_125") (pintype "passive"))
    )
    (net (code "154") (name "unconnected-(J2-Pad126)") (class "Default")
      (node (ref "J2") (pin "126") (pinfunction "126_126") (pintype "passive"))
    )
    (net (code "155") (name "unconnected-(J2-Pad128)") (class "Default")
      (node (ref "J2") (pin "128") (pinfunction "128_128") (pintype "passive"))
    )
    (net (code "156") (name "unconnected-(J2-Pad129)") (class "Default")
      (node (ref "J2") (pin "129") (pinfunction "129_129") (pintype "passive"))
    )
    (net (code "157") (name "unconnected-(J2-Pad132)") (class "Default")
      (node (ref "J2") (pin "132") (pinfunction "132_132") (pintype "passive"))
    )
    (net (code "158") (name "unconnected-(J2-Pad133)") (class "Default")
      (node (ref "J2") (pin "133") (pinfunction "133_133") (pintype "passive"))
    )
    (net (code "159") (name "unconnected-(J2-Pad135)") (class "Default")
      (node (ref "J2") (pin "135") (pinfunction "135_135") (pintype "passive"))
    )
    (net (code "160") (name "unconnected-(J2-Pad136)") (class "Default")
      (node (ref "J2") (pin "136") (pinfunction "136_136") (pintype "passive"))
    )
    (net (code "161") (name "unconnected-(J2-Pad138)") (class "Default")
      (node (ref "J2") (pin "138") (pinfunction "138_138") (pintype "passive"))
    )
    (net (code "162") (name "unconnected-(J2-Pad139)") (class "Default")
      (node (ref "J2") (pin "139") (pinfunction "139_139") (pintype "passive"))
    )
    (net (code "163") (name "unconnected-(J2-Pad142)") (class "Default")
      (node (ref "J2") (pin "142") (pinfunction "142_142") (pintype "passive"))
    )
    (net (code "164") (name "unconnected-(J2-Pad143)") (class "Default")
      (node (ref "J2") (pin "143") (pinfunction "143_143") (pintype "passive"))
    )
    (net (code "165") (name "unconnected-(J2-Pad145)") (class "Default")
      (node (ref "J2") (pin "145") (pinfunction "145_145") (pintype "passive"))
    )
    (net (code "166") (name "unconnected-(J2-Pad146)") (class "Default")
      (node (ref "J2") (pin "146") (pinfunction "146_146") (pintype "passive"))
    )
    (net (code "167") (name "unconnected-(J2-Pad148)") (class "Default")
      (node (ref "J2") (pin "148") (pinfunction "148_148") (pintype "passive"))
    )
    (net (code "168") (name "unconnected-(J2-Pad149)") (class "Default")
      (node (ref "J2") (pin "149") (pinfunction "149_149") (pintype "passive"))
    )
    (net (code "169") (name "unconnected-(J2-Pad152)") (class "Default")
      (node (ref "J2") (pin "152") (pinfunction "152_152") (pintype "passive"))
    )
    (net (code "170") (name "unconnected-(J2-Pad153)") (class "Default")
      (node (ref "J2") (pin "153") (pinfunction "153_153") (pintype "passive"))
    )
    (net (code "171") (name "unconnected-(J2-Pad155)") (class "Default")
      (node (ref "J2") (pin "155") (pinfunction "155_155") (pintype "passive"))
    )
    (net (code "172") (name "unconnected-(J2-Pad156)") (class "Default")
      (node (ref "J2") (pin "156") (pinfunction "156_156") (pintype "passive"))
    )
    (net (code "173") (name "unconnected-(J2-Pad158)") (class "Default")
      (node (ref "J2") (pin "158") (pinfunction "158_158") (pintype "passive"))
    )
    (net (code "174") (name "unconnected-(J2-Pad159)") (class "Default")
      (node (ref "J2") (pin "159") (pinfunction "159_159") (pintype "passive"))
    )
    (net (code "175") (name "unconnected-(J2-Pad319)") (class "Default")
      (node (ref "J2") (pin "319") (pinfunction "319_319") (pintype "passive+no_connect"))
    )
    (net (code "176") (name "unconnected-(J2-Pad322)") (class "Default")
      (node (ref "J2") (pin "322") (pinfunction "322_322") (pintype "passive"))
    )
    (net (code "177") (name "unconnected-(J2-Pad323)") (class "Default")
      (node (ref "J2") (pin "323") (pinfunction "323_323") (pintype "passive"))
    )
    (net (code "178") (name "unconnected-(J2-Pad325)") (class "Default")
      (node (ref "J2") (pin "325") (pinfunction "325_325") (pintype "passive"))
    )
    (net (code "179") (name "unconnected-(J2-Pad326)") (class "Default")
      (node (ref "J2") (pin "326") (pinfunction "326_326") (pintype "passive"))
    )
    (net (code "180") (name "unconnected-(J2-Pad328)") (class "Default")
      (node (ref "J2") (pin "328") (pinfunction "328_328") (pintype "passive"))
    )
    (net (code "181") (name "unconnected-(J2-Pad329)") (class "Default")
      (node (ref "J2") (pin "329") (pinfunction "329_329") (pintype "passive"))
    )
    (net (code "182") (name "unconnected-(J2-Pad332)") (class "Default")
      (node (ref "J2") (pin "332") (pinfunction "332_332") (pintype "passive"))
    )
    (net (code "183") (name "unconnected-(J2-Pad333)") (class "Default")
      (node (ref "J2") (pin "333") (pinfunction "333_333") (pintype "passive"))
    )
    (net (code "184") (name "unconnected-(J2-Pad335)") (class "Default")
      (node (ref "J2") (pin "335") (pinfunction "335_335") (pintype "passive"))
    )
    (net (code "185") (name "unconnected-(J2-Pad336)") (class "Default")
      (node (ref "J2") (pin "336") (pinfunction "336_336") (pintype "passive"))
    )
    (net (code "186") (name "unconnected-(J2-Pad338)") (class "Default")
      (node (ref "J2") (pin "338") (pinfunction "338_338") (pintype "passive"))
    )
    (net (code "187") (name "unconnected-(J2-Pad339)") (class "Default")
      (node (ref "J2") (pin "339") (pinfunction "339_339") (pintype "passive"))
    )
    (net (code "188") (name "unconnected-(J2-Pad342)") (class "Default")
      (node (ref "J2") (pin "342") (pinfunction "342_342") (pintype "passive"))
    )
    (net (code "189") (name "unconnected-(J2-Pad343)") (class "Default")
      (node (ref "J2") (pin "343") (pinfunction "343_343") (pintype "passive"))
    )
    (net (code "190") (name "unconnected-(J2-Pad345)") (class "Default")
      (node (ref "J2") (pin "345") (pinfunction "345_345") (pintype "passive"))
    )
    (net (code "191") (name "unconnected-(J2-Pad346)") (class "Default")
      (node (ref "J2") (pin "346") (pinfunction "346_346") (pintype "passive"))
    )
    (net (code "192") (name "unconnected-(J2-Pad348)") (class "Default")
      (node (ref "J2") (pin "348") (pinfunction "348_348") (pintype "passive"))
    )
    (net (code "193") (name "unconnected-(J2-Pad349)") (class "Default")
      (node (ref "J2") (pin "349") (pinfunction "349_349") (pintype "passive"))
    )
    (net (code "194") (name "unconnected-(J2-Pad352)") (class "Default")
      (node (ref "J2") (pin "352") (pinfunction "352_352") (pintype "passive"))
    )
    (net (code "195") (name "unconnected-(J2-Pad353)") (class "Default")
      (node (ref "J2") (pin "353") (pinfunction "353_353") (pintype "passive"))
    )
    (net (code "196") (name "unconnected-(J2-Pad355)") (class "Default")
      (node (ref "J2") (pin "355") (pinfunction "355_355") (pintype "passive"))
    )
    (net (code "197") (name "unconnected-(J2-Pad356)") (class "Default")
      (node (ref "J2") (pin "356") (pinfunction "356_356") (pintype "passive"))
    )
    (net (code "198") (name "unconnected-(J2-Pad358)") (class "Default")
      (node (ref "J2") (pin "358") (pinfunction "358_358") (pintype "passive"))
    )
    (net (code "199") (name "unconnected-(J2-Pad359)") (class "Default")
      (node (ref "J2") (pin "359") (pinfunction "359_359") (pintype "passive"))
    )
    (net (code "200") (name "unconnected-(J2-Pad362)") (class "Default")
      (node (ref "J2") (pin "362") (pinfunction "362_362") (pintype "passive"))
    )
    (net (code "201") (name "unconnected-(J2-Pad363)") (class "Default")
      (node (ref "J2") (pin "363") (pinfunction "363_363") (pintype "passive"))
    )
    (net (code "202") (name "unconnected-(J2-Pad365)") (class "Default")
      (node (ref "J2") (pin "365") (pinfunction "365_365") (pintype "passive"))
    )
    (net (code "203") (name "unconnected-(J2-Pad366)") (class "Default")
      (node (ref "J2") (pin "366") (pinfunction "366_366") (pintype "passive"))
    )
    (net (code "204") (name "unconnected-(J2-Pad368)") (class "Default")
      (node (ref "J2") (pin "368") (pinfunction "368_368") (pintype "passive"))
    )
    (net (code "205") (name "unconnected-(J2-Pad369)") (class "Default")
      (node (ref "J2") (pin "369") (pinfunction "369_369") (pintype "passive"))
    )
    (net (code "206") (name "unconnected-(J2-Pad372)") (class "Default")
      (node (ref "J2") (pin "372") (pinfunction "372_372") (pintype "passive"))
    )
    (net (code "207") (name "unconnected-(J2-Pad373)") (class "Default")
      (node (ref "J2") (pin "373") (pinfunction "373_373") (pintype "passive"))
    )
    (net (code "208") (name "unconnected-(J2-Pad375)") (class "Default")
      (node (ref "J2") (pin "375") (pinfunction "375_375") (pintype "passive"))
    )
    (net (code "209") (name "unconnected-(J2-Pad376)") (class "Default")
      (node (ref "J2") (pin "376") (pinfunction "376_376") (pintype "passive"))
    )
    (net (code "210") (name "unconnected-(J2-Pad378)") (class "Default")
      (node (ref "J2") (pin "378") (pinfunction "378_378") (pintype "passive"))
    )
    (net (code "211") (name "unconnected-(J2-Pad379)") (class "Default")
      (node (ref "J2") (pin "379") (pinfunction "379_379") (pintype "passive"))
    )
    (net (code "212") (name "unconnected-(J2-Pad382)") (class "Default")
      (node (ref "J2") (pin "382") (pinfunction "382_382") (pintype "passive"))
    )
    (net (code "213") (name "unconnected-(J2-Pad383)") (class "Default")
      (node (ref "J2") (pin "383") (pinfunction "383_383") (pintype "passive"))
    )
    (net (code "214") (name "unconnected-(J2-Pad385)") (class "Default")
      (node (ref "J2") (pin "385") (pinfunction "385_385") (pintype "passive"))
    )
    (net (code "215") (name "unconnected-(J2-Pad386)") (class "Default")
      (node (ref "J2") (pin "386") (pinfunction "386_386") (pintype "passive"))
    )
    (net (code "216") (name "unconnected-(J2-Pad388)") (class "Default")
      (node (ref "J2") (pin "388") (pinfunction "388_388") (pintype "passive"))
    )
    (net (code "217") (name "unconnected-(J2-Pad389)") (class "Default")
      (node (ref "J2") (pin "389") (pinfunction "389_389") (pintype "passive"))
    )
    (net (code "218") (name "unconnected-(J2-Pad392)") (class "Default")
      (node (ref "J2") (pin "392") (pinfunction "392_392") (pintype "passive"))
    )
    (net (code "219") (name "unconnected-(J2-Pad393)") (class "Default")
      (node (ref "J2") (pin "393") (pinfunction "393_393") (pintype "passive"))
    )
    (net (code "220") (name "unconnected-(J2-Pad395)") (class "Default")
      (node (ref "J2") (pin "395") (pinfunction "395_395") (pintype "passive"))
    )
    (net (code "221") (name "unconnected-(J2-Pad396)") (class "Default")
      (node (ref "J2") (pin "396") (pinfunction "396_396") (pintype "passive"))
    )
    (net (code "222") (name "unconnected-(J2-Pad398)") (class "Default")
      (node (ref "J2") (pin "398") (pinfunction "398_398") (pintype "passive"))
    )
    (net (code "223") (name "unconnected-(J2-Pad399)") (class "Default")
      (node (ref "J2") (pin "399") (pinfunction "399_399") (pintype "passive"))
    )
  )
)
